# UKU208_main.net
KiCad netlist of a schematic drawn in Altium Designer
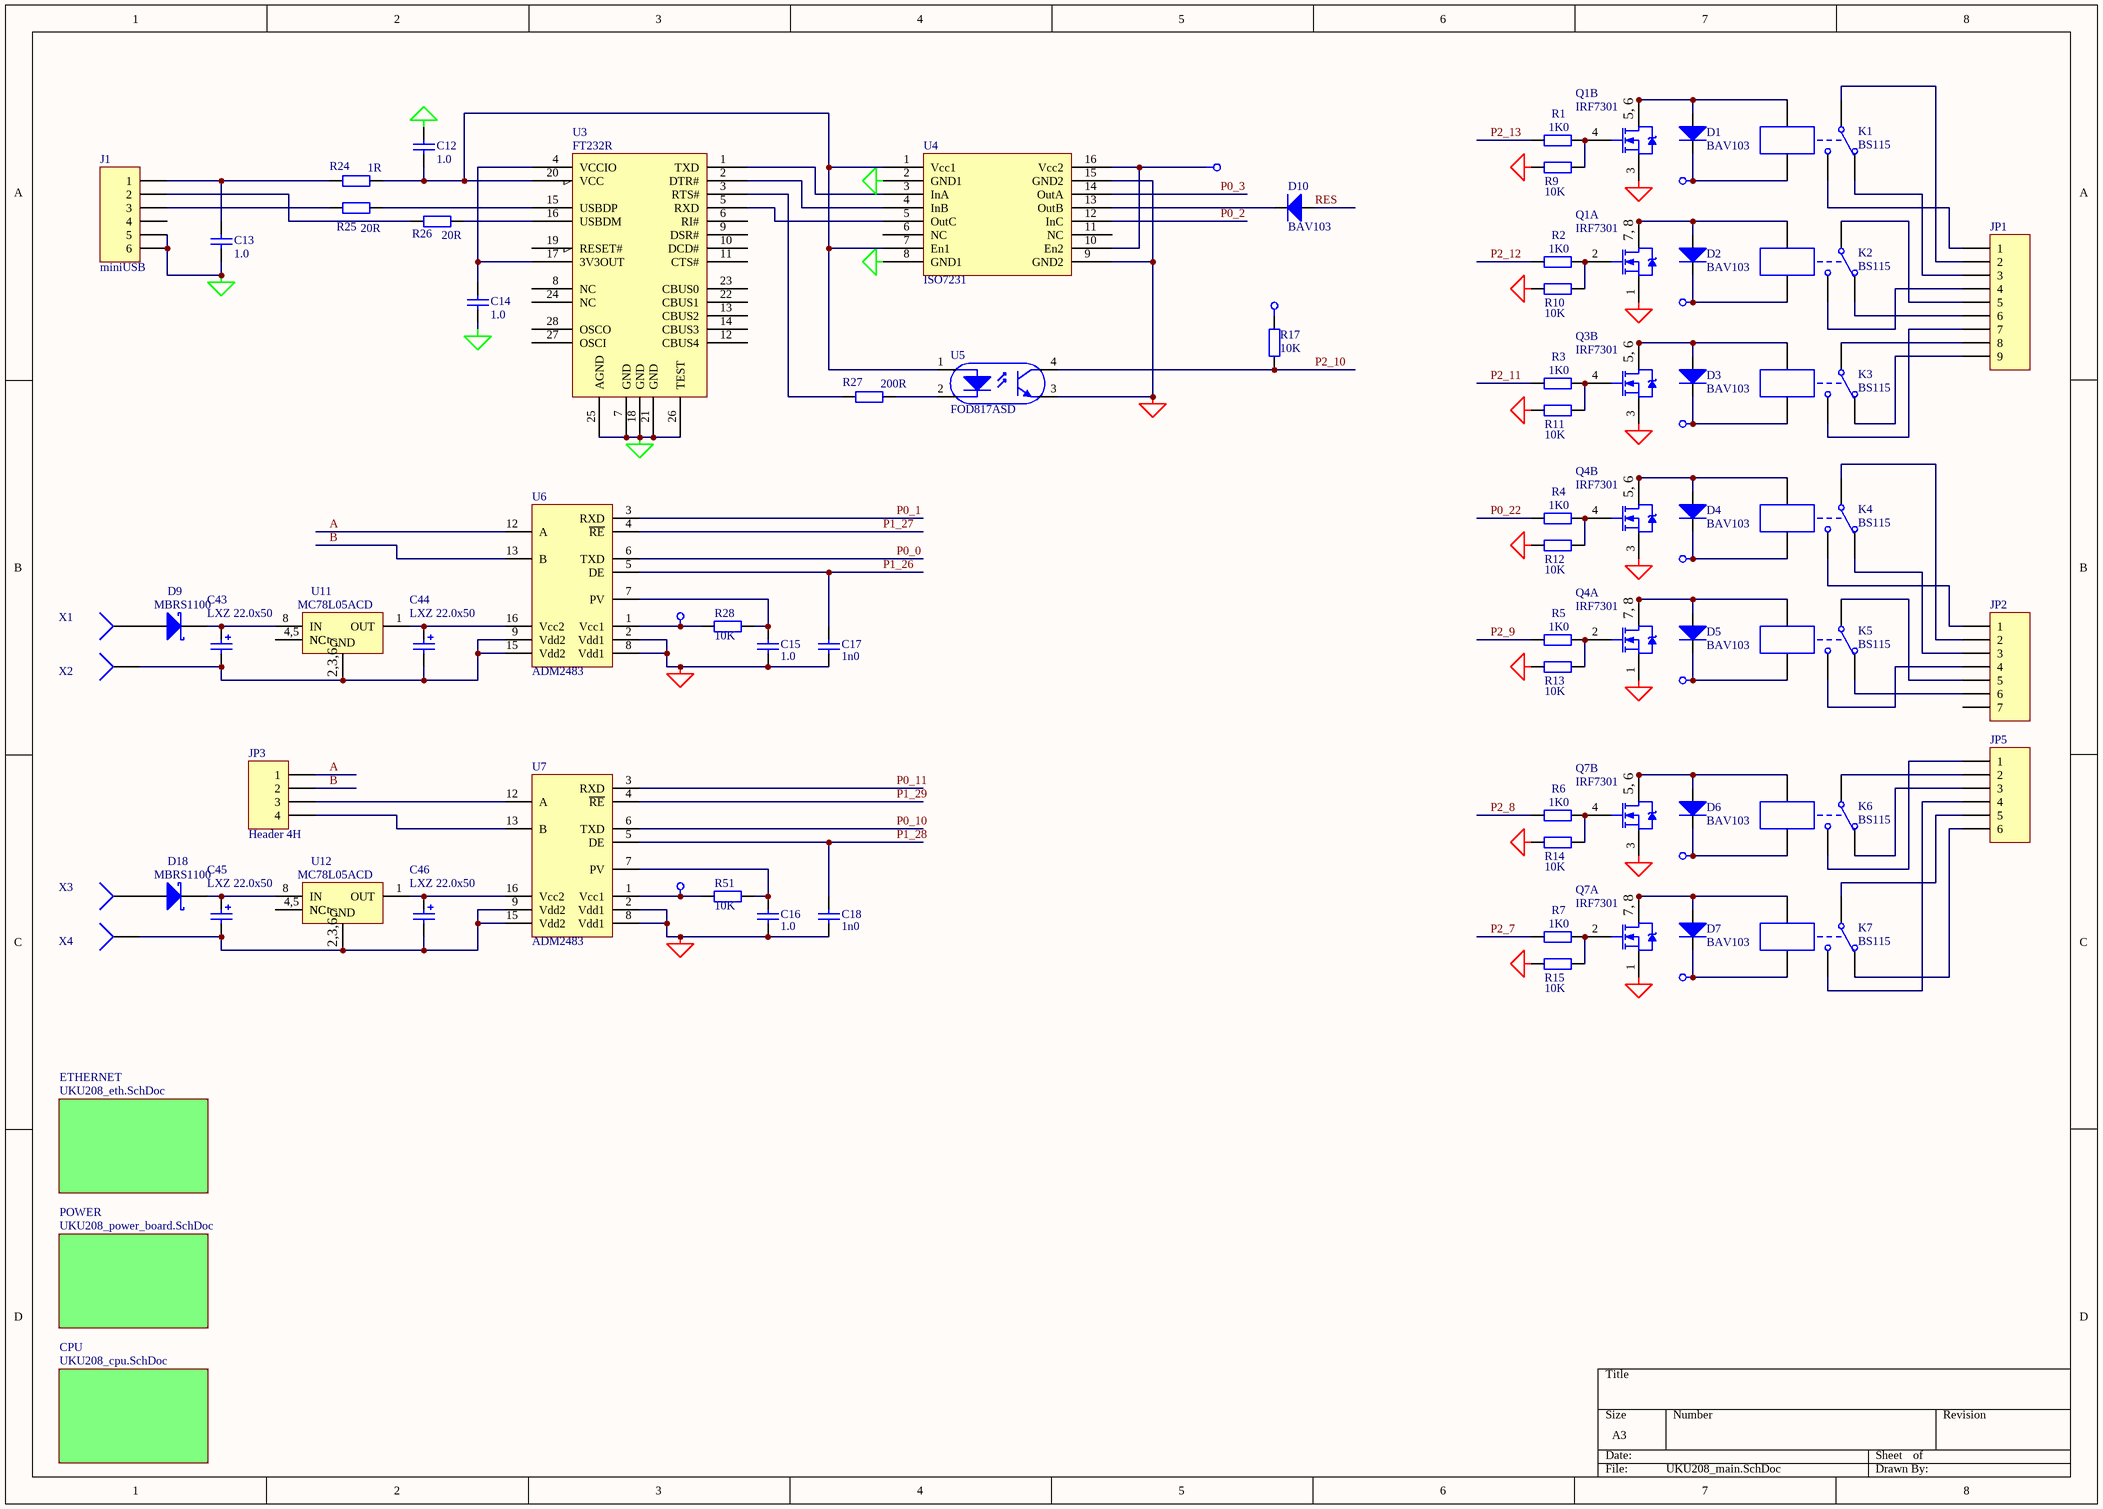
[diagram p0: UKU208_main.SchDoc]

(export (version "E")
  (design (tool "Eeschema 10.0.6"))
  (components
    (comp (ref "C12")
      (value "1.0")
      (footprint "_1206")
      (description "Capacitor (Semiconductor SIM Model)")
      (fields (field (name "MANUFACTURER") "Generic Components") (field (name "PUBLISHER") "Altium Limited"))
      (libsource (lib "Miscellaneous Devices") (part "Cap Semi"))
    )
    (comp (ref "C13")
      (value "1.0")
      (footprint "_1206")
      (description "Capacitor (Semiconductor SIM Model)")
      (fields (field (name "MANUFACTURER") "Generic Components") (field (name "PUBLISHER") "Altium Limited"))
      (libsource (lib "Miscellaneous Devices") (part "Cap Semi"))
    )
    (comp (ref "C14")
      (value "1.0")
      (footprint "_1206")
      (description "Capacitor (Semiconductor SIM Model)")
      (fields (field (name "MANUFACTURER") "Generic Components") (field (name "PUBLISHER") "Altium Limited"))
      (libsource (lib "Miscellaneous Devices") (part "Cap Semi"))
    )
    (comp (ref "C15")
      (value "1.0")
      (footprint "_1206")
      (description "Capacitor (Semiconductor SIM Model)")
      (fields (field (name "MANUFACTURER") "Generic Components") (field (name "PUBLISHER") "Altium Limited"))
      (libsource (lib "Miscellaneous Devices") (part "Cap Semi"))
    )
    (comp (ref "C16")
      (value "1.0")
      (footprint "_1206")
      (description "Capacitor (Semiconductor SIM Model)")
      (fields (field (name "MANUFACTURER") "Generic Components") (field (name "PUBLISHER") "Altium Limited"))
      (libsource (lib "Miscellaneous Devices") (part "Cap Semi"))
    )
    (comp (ref "C17")
      (value "1n0")
      (footprint "_1206")
      (description "Capacitor (Semiconductor SIM Model)")
      (fields (field (name "MANUFACTURER") "Generic Components") (field (name "PUBLISHER") "Altium Limited"))
      (libsource (lib "Miscellaneous Devices") (part "Cap Semi"))
    )
    (comp (ref "C18")
      (value "1n0")
      (footprint "_1206")
      (description "Capacitor (Semiconductor SIM Model)")
      (fields (field (name "MANUFACTURER") "Generic Components") (field (name "PUBLISHER") "Altium Limited"))
      (libsource (lib "Miscellaneous Devices") (part "Cap Semi"))
    )
    (comp (ref "C43")
      (value "LXZ 22.0x50")
      (footprint "el3")
      (description "Polarized Capacitor (Radial)")
      (fields (field (name "MANUFACTURER") "Generic Components") (field (name "PUBLISHER") "Altium Limited"))
      (libsource (lib "PAL") (part "Cap Pol1"))
    )
    (comp (ref "C44")
      (value "LXZ 22.0x50")
      (footprint "el3")
      (description "Polarized Capacitor (Radial)")
      (fields (field (name "MANUFACTURER") "Generic Components") (field (name "PUBLISHER") "Altium Limited"))
      (libsource (lib "PAL") (part "Cap Pol1"))
    )
    (comp (ref "C45")
      (value "LXZ 22.0x50")
      (footprint "el3")
      (description "Polarized Capacitor (Radial)")
      (fields (field (name "MANUFACTURER") "Generic Components") (field (name "PUBLISHER") "Altium Limited"))
      (libsource (lib "PAL") (part "Cap Pol1"))
    )
    (comp (ref "C46")
      (value "LXZ 22.0x50")
      (footprint "el3")
      (description "Polarized Capacitor (Radial)")
      (fields (field (name "MANUFACTURER") "Generic Components") (field (name "PUBLISHER") "Altium Limited"))
      (libsource (lib "PAL") (part "Cap Pol1"))
    )
    (comp (ref "D1")
      (value "BAV103")
      (footprint "_1206d")
      (description "Diode")
      (fields (field (name "MANUFACTURER") "Generic Components") (field (name "PUBLISHER") "Altium Limited"))
      (libsource (lib "PAL") (part "Diode"))
    )
    (comp (ref "D2")
      (value "BAV103")
      (footprint "_1206d")
      (description "Diode")
      (fields (field (name "MANUFACTURER") "Generic Components") (field (name "PUBLISHER") "Altium Limited"))
      (libsource (lib "PAL") (part "Diode"))
    )
    (comp (ref "D3")
      (value "BAV103")
      (footprint "_1206d")
      (description "Diode")
      (fields (field (name "MANUFACTURER") "Generic Components") (field (name "PUBLISHER") "Altium Limited"))
      (libsource (lib "PAL") (part "Diode"))
    )
    (comp (ref "D4")
      (value "BAV103")
      (footprint "_1206d")
      (description "Diode")
      (fields (field (name "MANUFACTURER") "Generic Components") (field (name "PUBLISHER") "Altium Limited"))
      (libsource (lib "PAL") (part "Diode"))
    )
    (comp (ref "D5")
      (value "BAV103")
      (footprint "_1206d")
      (description "Diode")
      (fields (field (name "MANUFACTURER") "Generic Components") (field (name "PUBLISHER") "Altium Limited"))
      (libsource (lib "PAL") (part "Diode"))
    )
    (comp (ref "D6")
      (value "BAV103")
      (footprint "_1206d")
      (description "Diode")
      (fields (field (name "MANUFACTURER") "Generic Components") (field (name "PUBLISHER") "Altium Limited"))
      (libsource (lib "PAL") (part "Diode"))
    )
    (comp (ref "D7")
      (value "BAV103")
      (footprint "_1206d")
      (description "Diode")
      (fields (field (name "MANUFACTURER") "Generic Components") (field (name "PUBLISHER") "Altium Limited"))
      (libsource (lib "PAL") (part "Diode"))
    )
    (comp (ref "D9")
      (value "MBRS1100")
      (footprint "D_6_3")
      (description "Schottky Rectifier")
      (fields
        (field (name "MANUFACTURER") "International Rectifier")
        (field (name "PUBLISHER") "Altium Limited")
      )
      (libsource (lib "IR Discrete Diode") (part "10BQ015"))
    )
    (comp (ref "D10")
      (value "BAV103")
      (footprint "_1206d")
      (description "Diode")
      (fields (field (name "MANUFACTURER") "Generic Components") (field (name "PUBLISHER") "Altium Limited"))
      (libsource (lib "PAL") (part "Diode"))
    )
    (comp (ref "D18")
      (value "MBRS1100")
      (footprint "D_6_3")
      (description "Schottky Rectifier")
      (fields
        (field (name "MANUFACTURER") "International Rectifier")
        (field (name "PUBLISHER") "Altium Limited")
      )
      (libsource (lib "IR Discrete Diode") (part "10BQ015"))
    )
    (comp (ref "J1")
      (value "miniUSB")
      (footprint "USBmini")
      (description "Header, 6-Pin")
      (fields (field (name "PUBLISHER") "Altium Limited"))
      (libsource (lib "Miscellaneous Connectors") (part "Header 6"))
    )
    (comp (ref "JP1")
      (value "MHDR1X9")
      (footprint "2EDGR-5.08-9P")
      (description "Header, 9-Pin")
      (fields (field (name "MANUFACTURER") "Generic Components") (field (name "PUBLISHER") "Altium Limited"))
      (libsource (lib "Miscellaneous Connectors") (part "MHDR1X9"))
    )
    (comp (ref "JP2")
      (value "MHDR1X7")
      (footprint "2EDGR-5.08-7P")
      (description "Header, 7-Pin")
      (fields (field (name "MANUFACTURER") "Generic Components") (field (name "PUBLISHER") "Altium Limited"))
      (libsource (lib "Miscellaneous Connectors") (part "MHDR1X7"))
    )
    (comp (ref "JP3")
      (value "Header 4H")
      (footprint "2EDGR-5.08-4P")
      (description "Header, 4-Pin,  Right Angle")
      (fields (field (name "MANUFACTURER") "Generic Components") (field (name "PUBLISHER") "Altium Limited"))
      (libsource (lib "Miscellaneous Connectors") (part "Header 4H"))
    )
    (comp (ref "JP5")
      (value "MHDR1X6")
      (footprint "2EDGR-5.08-6P")
      (description "Header, 6-Pin")
      (fields (field (name "MANUFACTURER") "Generic Components") (field (name "PUBLISHER") "Altium Limited"))
      (libsource (lib "Miscellaneous Connectors") (part "MHDR1X6"))
    )
    (comp (ref "K1")
      (value "BS115")
      (footprint "bs115")
      (description "Single-Pole Dual-Throw Relay")
      (fields (field (name "MANUFACTURER") "Generic Components") (field (name "PUBLISHER") "Altium Limited"))
      (libsource (lib "PAL") (part "BS115"))
    )
    (comp (ref "K2")
      (value "BS115")
      (footprint "bs115")
      (description "Single-Pole Dual-Throw Relay")
      (fields (field (name "MANUFACTURER") "Generic Components") (field (name "PUBLISHER") "Altium Limited"))
      (libsource (lib "PAL") (part "BS115"))
    )
    (comp (ref "K3")
      (value "BS115")
      (footprint "bs115")
      (description "Single-Pole Dual-Throw Relay")
      (fields (field (name "MANUFACTURER") "Generic Components") (field (name "PUBLISHER") "Altium Limited"))
      (libsource (lib "PAL") (part "BS115"))
    )
    (comp (ref "K4")
      (value "BS115")
      (footprint "bs115")
      (description "Single-Pole Dual-Throw Relay")
      (fields (field (name "MANUFACTURER") "Generic Components") (field (name "PUBLISHER") "Altium Limited"))
      (libsource (lib "PAL") (part "BS115"))
    )
    (comp (ref "K5")
      (value "BS115")
      (footprint "bs115")
      (description "Single-Pole Dual-Throw Relay")
      (fields (field (name "MANUFACTURER") "Generic Components") (field (name "PUBLISHER") "Altium Limited"))
      (libsource (lib "PAL") (part "BS115"))
    )
    (comp (ref "K6")
      (value "BS115")
      (footprint "bs115")
      (description "Single-Pole Dual-Throw Relay")
      (fields (field (name "MANUFACTURER") "Generic Components") (field (name "PUBLISHER") "Altium Limited"))
      (libsource (lib "PAL") (part "BS115"))
    )
    (comp (ref "K7")
      (value "BS115")
      (footprint "bs115")
      (description "Single-Pole Dual-Throw Relay")
      (fields (field (name "MANUFACTURER") "Generic Components") (field (name "PUBLISHER") "Altium Limited"))
      (libsource (lib "PAL") (part "BS115"))
    )
    (comp (ref "Q1")
      (value "IRF7301")
      (footprint "SO-G8/Y2.2")
      (description "FET")
      (fields
        (field (name "MANUFACTURER") "International Rectifier")
        (field (name "PUBLISHER") "Altium Limited")
      )
      (libsource (lib "IR Discrete MOSFET") (part "IRF7301"))
    )
    (comp (ref "Q3")
      (value "IRF7301")
      (footprint "SO-G8/Y2.2")
      (description "FET")
      (fields
        (field (name "MANUFACTURER") "International Rectifier")
        (field (name "PUBLISHER") "Altium Limited")
      )
      (libsource (lib "IR Discrete MOSFET") (part "IRF7301"))
    )
    (comp (ref "Q4")
      (value "IRF7301")
      (footprint "SO-G8/Y2.2")
      (description "FET")
      (fields
        (field (name "MANUFACTURER") "International Rectifier")
        (field (name "PUBLISHER") "Altium Limited")
      )
      (libsource (lib "IR Discrete MOSFET") (part "IRF7301"))
    )
    (comp (ref "Q7")
      (value "IRF7301")
      (footprint "SO-G8/Y2.2")
      (description "FET")
      (fields
        (field (name "MANUFACTURER") "International Rectifier")
        (field (name "PUBLISHER") "Altium Limited")
      )
      (libsource (lib "IR Discrete MOSFET") (part "IRF7301"))
    )
    (comp (ref "R1")
      (value "1K0")
      (footprint "_1206")
      (description "Resistor")
      (fields (field (name "MANUFACTURER") "Generic Components") (field (name "PUBLISHER") "Altium Limited"))
      (libsource (lib "Miscellaneous Devices") (part "Res2"))
    )
    (comp (ref "R2")
      (value "1K0")
      (footprint "_1206")
      (description "Resistor")
      (fields (field (name "MANUFACTURER") "Generic Components") (field (name "PUBLISHER") "Altium Limited"))
      (libsource (lib "Miscellaneous Devices") (part "Res2"))
    )
    (comp (ref "R3")
      (value "1K0")
      (footprint "_1206")
      (description "Resistor")
      (fields (field (name "MANUFACTURER") "Generic Components") (field (name "PUBLISHER") "Altium Limited"))
      (libsource (lib "Miscellaneous Devices") (part "Res2"))
    )
    (comp (ref "R4")
      (value "1K0")
      (footprint "_1206")
      (description "Resistor")
      (fields (field (name "MANUFACTURER") "Generic Components") (field (name "PUBLISHER") "Altium Limited"))
      (libsource (lib "Miscellaneous Devices") (part "Res2"))
    )
    (comp (ref "R5")
      (value "1K0")
      (footprint "_1206")
      (description "Resistor")
      (fields (field (name "MANUFACTURER") "Generic Components") (field (name "PUBLISHER") "Altium Limited"))
      (libsource (lib "Miscellaneous Devices") (part "Res2"))
    )
    (comp (ref "R6")
      (value "1K0")
      (footprint "_1206")
      (description "Resistor")
      (fields (field (name "MANUFACTURER") "Generic Components") (field (name "PUBLISHER") "Altium Limited"))
      (libsource (lib "Miscellaneous Devices") (part "Res2"))
    )
    (comp (ref "R7")
      (value "1K0")
      (footprint "_1206")
      (description "Resistor")
      (fields (field (name "MANUFACTURER") "Generic Components") (field (name "PUBLISHER") "Altium Limited"))
      (libsource (lib "Miscellaneous Devices") (part "Res2"))
    )
    (comp (ref "R9")
      (value "10K")
      (footprint "_1206")
      (description "Resistor")
      (fields (field (name "MANUFACTURER") "Generic Components") (field (name "PUBLISHER") "Altium Limited"))
      (libsource (lib "Miscellaneous Devices") (part "Res2"))
    )
    (comp (ref "R10")
      (value "10K")
      (footprint "_1206")
      (description "Resistor")
      (fields (field (name "MANUFACTURER") "Generic Components") (field (name "PUBLISHER") "Altium Limited"))
      (libsource (lib "Miscellaneous Devices") (part "Res2"))
    )
    (comp (ref "R11")
      (value "10K")
      (footprint "_1206")
      (description "Resistor")
      (fields (field (name "MANUFACTURER") "Generic Components") (field (name "PUBLISHER") "Altium Limited"))
      (libsource (lib "Miscellaneous Devices") (part "Res2"))
    )
    (comp (ref "R12")
      (value "10K")
      (footprint "_1206")
      (description "Resistor")
      (fields (field (name "MANUFACTURER") "Generic Components") (field (name "PUBLISHER") "Altium Limited"))
      (libsource (lib "Miscellaneous Devices") (part "Res2"))
    )
    (comp (ref "R13")
      (value "10K")
      (footprint "_1206")
      (description "Resistor")
      (fields (field (name "MANUFACTURER") "Generic Components") (field (name "PUBLISHER") "Altium Limited"))
      (libsource (lib "Miscellaneous Devices") (part "Res2"))
    )
    (comp (ref "R14")
      (value "10K")
      (footprint "_1206")
      (description "Resistor")
      (fields (field (name "MANUFACTURER") "Generic Components") (field (name "PUBLISHER") "Altium Limited"))
      (libsource (lib "Miscellaneous Devices") (part "Res2"))
    )
    (comp (ref "R15")
      (value "10K")
      (footprint "_1206")
      (description "Resistor")
      (fields (field (name "MANUFACTURER") "Generic Components") (field (name "PUBLISHER") "Altium Limited"))
      (libsource (lib "Miscellaneous Devices") (part "Res2"))
    )
    (comp (ref "R17")
      (value "10K")
      (footprint "_1206")
      (description "Resistor")
      (fields (field (name "MANUFACTURER") "Generic Components") (field (name "PUBLISHER") "Altium Limited"))
      (libsource (lib "") (part "Res2_1"))
    )
    (comp (ref "R24") (value "1R") (footprint "_1206") (libsource (lib "igorenja") (part "RES")))
    (comp (ref "R25") (value "20R") (footprint "_1206") (libsource (lib "igorenja") (part "RES")))
    (comp (ref "R26") (value "20R") (footprint "_1206") (libsource (lib "igorenja") (part "RES")))
    (comp (ref "R27") (value "200R") (footprint "_1206") (libsource (lib "igorenja") (part "RES")))
    (comp (ref "R28")
      (value "10K")
      (footprint "_1206")
      (description "Resistor")
      (fields (field (name "MANUFACTURER") "Generic Components") (field (name "PUBLISHER") "Altium Limited"))
      (libsource (lib "") (part "Res2_2"))
    )
    (comp (ref "R51")
      (value "10K")
      (footprint "_1206")
      (description "Resistor")
      (fields (field (name "MANUFACTURER") "Generic Components") (field (name "PUBLISHER") "Altium Limited"))
      (libsource (lib "") (part "Res2_2"))
    )
    (comp (ref "U3")
      (value "FT232R")
      (footprint "SOP65P780-28L")
      (libsource (lib "igorenja") (part "FT232R"))
    )
    (comp (ref "U4") (value "ISO7231") (footprint "SO-G16/D10.4") (libsource (lib "PAL") (part "ISO7231")))
    (comp (ref "U5") (value "FOD817ASD") (footprint "FOD817ASD") (libsource (lib "PAL") (part "F00817ASD")))
    (comp (ref "U6") (value "ADM2483") (footprint "SO-G16/D10.4") (libsource (lib "PAL") (part "ADM2483")))
    (comp (ref "U7") (value "ADM2483") (footprint "SO-G16/D10.4") (libsource (lib "PAL") (part "ADM2483")))
    (comp (ref "U11")
      (value "MC78L05ACD")
      (footprint "SO-G8")
      (description "3-Terminal Low-Current Positive Fixed Voltage Regulator")
      (fields (field (name "MANUFACTURER") "Motorola") (field (name "PUBLISHER") "Altium Limited"))
      (libsource (lib "Motorola Power Management Voltage Regulator") (part "MC78L05ACD"))
    )
    (comp (ref "U12")
      (value "MC78L05ACD")
      (footprint "SO-G8")
      (description "3-Terminal Low-Current Positive Fixed Voltage Regulator")
      (fields (field (name "MANUFACTURER") "Motorola") (field (name "PUBLISHER") "Altium Limited"))
      (libsource (lib "Motorola Power Management Voltage Regulator") (part "MC78L05ACD"))
    )
    (comp (ref "X1")
      (value "~")
      (footprint "PIN1")
      (description "Socket")
      (fields (field (name "MANUFACTURER") "Generic Components") (field (name "PUBLISHER") "Altium Limited"))
      (libsource (lib "Miscellaneous Connectors") (part "Socket"))
    )
    (comp (ref "X2")
      (value "~")
      (footprint "PIN1")
      (description "Socket")
      (fields (field (name "MANUFACTURER") "Generic Components") (field (name "PUBLISHER") "Altium Limited"))
      (libsource (lib "Miscellaneous Connectors") (part "Socket"))
    )
    (comp (ref "X3")
      (value "~")
      (footprint "PIN1")
      (description "Socket")
      (fields (field (name "MANUFACTURER") "Generic Components") (field (name "PUBLISHER") "Altium Limited"))
      (libsource (lib "Miscellaneous Connectors") (part "Socket"))
    )
    (comp (ref "X4")
      (value "~")
      (footprint "PIN1")
      (description "Socket")
      (fields (field (name "MANUFACTURER") "Generic Components") (field (name "PUBLISHER") "Altium Limited"))
      (libsource (lib "Miscellaneous Connectors") (part "Socket"))
    )
  )
  (nets
    (net (code "1") (name "+3v3") (class "Default")
      (node (ref "R17") (pin "2") (pinfunction "2_2") (pintype "passive"))
    )
    (net (code "2") (name "+5v") (class "Default")
      (node (ref "D1") (pin "2") (pinfunction "K_2") (pintype "passive"))
      (node (ref "D2") (pin "2") (pinfunction "K_2") (pintype "passive"))
      (node (ref "D3") (pin "2") (pinfunction "K_2") (pintype "passive"))
      (node (ref "D4") (pin "2") (pinfunction "K_2") (pintype "passive"))
      (node (ref "D5") (pin "2") (pinfunction "K_2") (pintype "passive"))
      (node (ref "D6") (pin "2") (pinfunction "K_2") (pintype "passive"))
      (node (ref "D7") (pin "2") (pinfunction "K_2") (pintype "passive"))
      (node (ref "K1") (pin "5") (pinfunction "5_5") (pintype "passive"))
      (node (ref "K2") (pin "5") (pinfunction "5_5") (pintype "passive"))
      (node (ref "K3") (pin "5") (pinfunction "5_5") (pintype "passive"))
      (node (ref "K4") (pin "5") (pinfunction "5_5") (pintype "passive"))
      (node (ref "K5") (pin "5") (pinfunction "5_5") (pintype "passive"))
      (node (ref "K6") (pin "5") (pinfunction "5_5") (pintype "passive"))
      (node (ref "K7") (pin "5") (pinfunction "5_5") (pintype "passive"))
      (node (ref "R28") (pin "1") (pinfunction "1_1") (pintype "passive"))
      (node (ref "R51") (pin "1") (pinfunction "1_1") (pintype "passive"))
      (node (ref "U4") (pin "10") (pinfunction "En2_10") (pintype "passive"))
      (node (ref "U4") (pin "16") (pinfunction "Vcc2_16") (pintype "passive"))
      (node (ref "U6") (pin "1") (pinfunction "Vcc1_1") (pintype "passive"))
      (node (ref "U7") (pin "1") (pinfunction "Vcc1_1") (pintype "passive"))
    )
    (net (code "3") (name "/A") (class "Default")
      (node (ref "JP3") (pin "1") (pinfunction "1_1") (pintype "passive"))
      (node (ref "U6") (pin "12") (pinfunction "A_12") (pintype "passive"))
    )
    (net (code "4") (name "/B") (class "Default")
      (node (ref "JP3") (pin "2") (pinfunction "2_2") (pintype "passive"))
      (node (ref "U6") (pin "13") (pinfunction "B_13") (pintype "passive"))
    )
    (net (code "5") (name "/P0_0") (class "Default")
      (node (ref "U6") (pin "6") (pinfunction "TXD_6") (pintype "passive"))
    )
    (net (code "6") (name "/P0_1") (class "Default")
      (node (ref "U6") (pin "3") (pinfunction "RXD_3") (pintype "passive"))
    )
    (net (code "7") (name "/P0_2") (class "Default")
      (node (ref "U4") (pin "12") (pinfunction "InC_12") (pintype "passive"))
    )
    (net (code "8") (name "/P0_3") (class "Default")
      (node (ref "U4") (pin "14") (pinfunction "OutA_14") (pintype "passive"))
    )
    (net (code "9") (name "/P0_10") (class "Default")
      (node (ref "U7") (pin "6") (pinfunction "TXD_6") (pintype "passive"))
    )
    (net (code "10") (name "/P0_11") (class "Default")
      (node (ref "U7") (pin "3") (pinfunction "RXD_3") (pintype "passive"))
    )
    (net (code "11") (name "/P0_22") (class "Default")
      (node (ref "R4") (pin "1") (pinfunction "1_1") (pintype "passive"))
    )
    (net (code "12") (name "/P1_26") (class "Default")
      (node (ref "C17") (pin "2") (pinfunction "2_2") (pintype "passive"))
      (node (ref "U6") (pin "5") (pinfunction "DE_5") (pintype "passive"))
    )
    (net (code "13") (name "/P1_27") (class "Default")
      (node (ref "U6") (pin "4") (pinfunction "~{RE}_4") (pintype "passive"))
    )
    (net (code "14") (name "/P1_28") (class "Default")
      (node (ref "C18") (pin "2") (pinfunction "2_2") (pintype "passive"))
      (node (ref "U7") (pin "5") (pinfunction "DE_5") (pintype "passive"))
    )
    (net (code "15") (name "/P1_29") (class "Default")
      (node (ref "U7") (pin "4") (pinfunction "~{RE}_4") (pintype "passive"))
    )
    (net (code "16") (name "/P2_7") (class "Default")
      (node (ref "R7") (pin "1") (pinfunction "1_1") (pintype "passive"))
    )
    (net (code "17") (name "/P2_8") (class "Default")
      (node (ref "R6") (pin "1") (pinfunction "1_1") (pintype "passive"))
    )
    (net (code "18") (name "/P2_9") (class "Default")
      (node (ref "R5") (pin "1") (pinfunction "1_1") (pintype "passive"))
    )
    (net (code "19") (name "/P2_10") (class "Default")
      (node (ref "R17") (pin "1") (pinfunction "1_1") (pintype "passive"))
      (node (ref "U5") (pin "4") (pinfunction "2_4") (pintype "passive"))
    )
    (net (code "20") (name "/P2_11") (class "Default")
      (node (ref "R3") (pin "1") (pinfunction "1_1") (pintype "passive"))
    )
    (net (code "21") (name "/P2_12") (class "Default")
      (node (ref "R2") (pin "1") (pinfunction "1_1") (pintype "passive"))
    )
    (net (code "22") (name "/P2_13") (class "Default")
      (node (ref "R1") (pin "1") (pinfunction "1_1") (pintype "passive"))
    )
    (net (code "23") (name "/RES") (class "Default")
      (node (ref "D10") (pin "1") (pinfunction "A_1") (pintype "passive"))
    )
    (net (code "24") (name "GND") (class "Default")
      (node (ref "C15") (pin "1") (pinfunction "1_1") (pintype "passive"))
      (node (ref "C16") (pin "1") (pinfunction "1_1") (pintype "passive"))
      (node (ref "C17") (pin "1") (pinfunction "1_1") (pintype "passive"))
      (node (ref "C18") (pin "1") (pinfunction "1_1") (pintype "passive"))
      (node (ref "Q1") (pin "1") (pinfunction "S_1") (pintype "passive"))
      (node (ref "Q1") (pin "3") (pinfunction "S_3") (pintype "passive"))
      (node (ref "Q3") (pin "3") (pinfunction "S_3") (pintype "passive"))
      (node (ref "Q4") (pin "1") (pinfunction "S_1") (pintype "passive"))
      (node (ref "Q4") (pin "3") (pinfunction "S_3") (pintype "passive"))
      (node (ref "Q7") (pin "1") (pinfunction "S_1") (pintype "passive"))
      (node (ref "Q7") (pin "3") (pinfunction "S_3") (pintype "passive"))
      (node (ref "R10") (pin "1") (pinfunction "1_1") (pintype "passive"))
      (node (ref "R11") (pin "1") (pinfunction "1_1") (pintype "passive"))
      (node (ref "R12") (pin "1") (pinfunction "1_1") (pintype "passive"))
      (node (ref "R13") (pin "1") (pinfunction "1_1") (pintype "passive"))
      (node (ref "R14") (pin "1") (pinfunction "1_1") (pintype "passive"))
      (node (ref "R15") (pin "1") (pinfunction "1_1") (pintype "passive"))
      (node (ref "R9") (pin "1") (pinfunction "1_1") (pintype "passive"))
      (node (ref "U4") (pin "15") (pinfunction "GND2_15") (pintype "passive"))
      (node (ref "U4") (pin "9") (pinfunction "GND2_9") (pintype "passive"))
      (node (ref "U5") (pin "3") (pinfunction "4_3") (pintype "passive"))
      (node (ref "U6") (pin "2") (pinfunction "Vdd1_2") (pintype "passive"))
      (node (ref "U6") (pin "8") (pinfunction "Vdd1_8") (pintype "passive"))
      (node (ref "U7") (pin "2") (pinfunction "Vdd1_2") (pintype "passive"))
      (node (ref "U7") (pin "8") (pinfunction "Vdd1_8") (pintype "passive"))
    )
    (net (code "25") (name "GND_USB") (class "Default")
      (node (ref "C12") (pin "1") (pinfunction "1_1") (pintype "passive"))
      (node (ref "C13") (pin "1") (pinfunction "1_1") (pintype "passive"))
      (node (ref "C14") (pin "1") (pinfunction "1_1") (pintype "passive"))
      (node (ref "J1") (pin "5") (pinfunction "5_5") (pintype "passive"))
      (node (ref "J1") (pin "6") (pinfunction "6_6") (pintype "passive"))
      (node (ref "U3") (pin "18") (pinfunction "GND_18") (pintype "passive"))
      (node (ref "U3") (pin "21") (pinfunction "GND_21") (pintype "passive"))
      (node (ref "U3") (pin "25") (pinfunction "AGND_25") (pintype "passive"))
      (node (ref "U3") (pin "26") (pinfunction "TEST_26") (pintype "passive"))
      (node (ref "U3") (pin "7") (pinfunction "GND_7") (pintype "passive"))
      (node (ref "U4") (pin "2") (pinfunction "GND1_2") (pintype "passive"))
      (node (ref "U4") (pin "8") (pinfunction "GND1_8") (pintype "passive"))
    )
    (net (code "26") (name "Net-(C13-Pad2)") (class "Default")
      (node (ref "C13") (pin "2") (pinfunction "2_2") (pintype "passive"))
      (node (ref "J1") (pin "1") (pinfunction "1_1") (pintype "passive"))
      (node (ref "R24") (pin "1") (pinfunction "1_1") (pintype "passive"))
    )
    (net (code "27") (name "Net-(C43-Pad2)") (class "Default")
      (node (ref "C43") (pin "2") (pinfunction "2_2") (pintype "passive"))
      (node (ref "C44") (pin "2") (pinfunction "2_2") (pintype "passive"))
      (node (ref "U11") (pin "2") (pinfunction "GND_2") (pintype "power_in"))
      (node (ref "U11") (pin "3") (pinfunction "GND_3") (pintype "power_in"))
      (node (ref "U11") (pin "6") (pinfunction "GND_6") (pintype "power_in"))
      (node (ref "U11") (pin "7") (pinfunction "GND_7") (pintype "power_in"))
      (node (ref "U6") (pin "15") (pinfunction "Vdd2_15") (pintype "passive"))
      (node (ref "U6") (pin "9") (pinfunction "Vdd2_9") (pintype "passive"))
      (node (ref "X2") (pin "1") (pinfunction "1_1") (pintype "passive"))
    )
    (net (code "28") (name "Net-(C45-Pad2)") (class "Default")
      (node (ref "C45") (pin "2") (pinfunction "2_2") (pintype "passive"))
      (node (ref "C46") (pin "2") (pinfunction "2_2") (pintype "passive"))
      (node (ref "U12") (pin "2") (pinfunction "GND_2") (pintype "power_in"))
      (node (ref "U12") (pin "3") (pinfunction "GND_3") (pintype "power_in"))
      (node (ref "U12") (pin "6") (pinfunction "GND_6") (pintype "power_in"))
      (node (ref "U12") (pin "7") (pinfunction "GND_7") (pintype "power_in"))
      (node (ref "U7") (pin "15") (pinfunction "Vdd2_15") (pintype "passive"))
      (node (ref "U7") (pin "9") (pinfunction "Vdd2_9") (pintype "passive"))
      (node (ref "X4") (pin "1") (pinfunction "1_1") (pintype "passive"))
    )
    (net (code "29") (name "Net-(D1-A)") (class "Default")
      (node (ref "D1") (pin "1") (pinfunction "A_1") (pintype "passive"))
      (node (ref "K1") (pin "4") (pinfunction "4_4") (pintype "passive"))
      (node (ref "Q1") (pin "5") (pinfunction "D_5") (pintype "passive"))
      (node (ref "Q1") (pin "6") (pinfunction "D_6") (pintype "passive"))
    )
    (net (code "30") (name "Net-(D2-A)") (class "Default")
      (node (ref "D2") (pin "1") (pinfunction "A_1") (pintype "passive"))
      (node (ref "K2") (pin "4") (pinfunction "4_4") (pintype "passive"))
      (node (ref "Q1") (pin "7") (pinfunction "D_7") (pintype "passive"))
      (node (ref "Q1") (pin "8") (pinfunction "D_8") (pintype "passive"))
    )
    (net (code "31") (name "Net-(D3-A)") (class "Default")
      (node (ref "D3") (pin "1") (pinfunction "A_1") (pintype "passive"))
      (node (ref "K3") (pin "4") (pinfunction "4_4") (pintype "passive"))
      (node (ref "Q3") (pin "5") (pinfunction "D_5") (pintype "passive"))
      (node (ref "Q3") (pin "6") (pinfunction "D_6") (pintype "passive"))
    )
    (net (code "32") (name "Net-(D4-A)") (class "Default")
      (node (ref "D4") (pin "1") (pinfunction "A_1") (pintype "passive"))
      (node (ref "K4") (pin "4") (pinfunction "4_4") (pintype "passive"))
      (node (ref "Q4") (pin "5") (pinfunction "D_5") (pintype "passive"))
      (node (ref "Q4") (pin "6") (pinfunction "D_6") (pintype "passive"))
    )
    (net (code "33") (name "Net-(D5-A)") (class "Default")
      (node (ref "D5") (pin "1") (pinfunction "A_1") (pintype "passive"))
      (node (ref "K5") (pin "4") (pinfunction "4_4") (pintype "passive"))
      (node (ref "Q4") (pin "7") (pinfunction "D_7") (pintype "passive"))
      (node (ref "Q4") (pin "8") (pinfunction "D_8") (pintype "passive"))
    )
    (net (code "34") (name "Net-(D6-A)") (class "Default")
      (node (ref "D6") (pin "1") (pinfunction "A_1") (pintype "passive"))
      (node (ref "K6") (pin "4") (pinfunction "4_4") (pintype "passive"))
      (node (ref "Q7") (pin "5") (pinfunction "D_5") (pintype "passive"))
      (node (ref "Q7") (pin "6") (pinfunction "D_6") (pintype "passive"))
    )
    (net (code "35") (name "Net-(D7-A)") (class "Default")
      (node (ref "D7") (pin "1") (pinfunction "A_1") (pintype "passive"))
      (node (ref "K7") (pin "4") (pinfunction "4_4") (pintype "passive"))
      (node (ref "Q7") (pin "7") (pinfunction "D_7") (pintype "passive"))
      (node (ref "Q7") (pin "8") (pinfunction "D_8") (pintype "passive"))
    )
    (net (code "36") (name "Net-(D9-A)") (class "Default")
      (node (ref "D9") (pin "1") (pinfunction "A_1") (pintype "passive"))
      (node (ref "X1") (pin "1") (pinfunction "1_1") (pintype "passive"))
    )
    (net (code "37") (name "Net-(D9-K)") (class "Default")
      (node (ref "C43") (pin "1") (pinfunction "1_1") (pintype "passive"))
      (node (ref "D9") (pin "2") (pinfunction "K_2") (pintype "passive"))
      (node (ref "U11") (pin "8") (pinfunction "IN_8") (pintype "power_in"))
    )
    (net (code "38") (name "Net-(D10-K)") (class "Default")
      (node (ref "D10") (pin "2") (pinfunction "K_2") (pintype "passive"))
      (node (ref "U4") (pin "13") (pinfunction "OutB_13") (pintype "passive"))
    )
    (net (code "39") (name "Net-(D18-A)") (class "Default")
      (node (ref "D18") (pin "1") (pinfunction "A_1") (pintype "passive"))
      (node (ref "X3") (pin "1") (pinfunction "1_1") (pintype "passive"))
    )
    (net (code "40") (name "Net-(D18-K)") (class "Default")
      (node (ref "C45") (pin "1") (pinfunction "1_1") (pintype "passive"))
      (node (ref "D18") (pin "2") (pinfunction "K_2") (pintype "passive"))
      (node (ref "U12") (pin "8") (pinfunction "IN_8") (pintype "power_in"))
    )
    (net (code "41") (name "Net-(J1-Pad2)") (class "Default")
      (node (ref "J1") (pin "2") (pinfunction "2_2") (pintype "passive"))
      (node (ref "R26") (pin "1") (pinfunction "1_1") (pintype "passive"))
    )
    (net (code "42") (name "Net-(J1-Pad3)") (class "Default")
      (node (ref "J1") (pin "3") (pinfunction "3_3") (pintype "passive"))
      (node (ref "R25") (pin "1") (pinfunction "1_1") (pintype "passive"))
    )
    (net (code "43") (name "Net-(JP1-Pad1)") (class "Default")
      (node (ref "JP1") (pin "1") (pinfunction "1_1") (pintype "passive"))
      (node (ref "K1") (pin "3") (pinfunction "3_3") (pintype "passive"))
    )
    (net (code "44") (name "Net-(JP1-Pad2)") (class "Default")
      (node (ref "JP1") (pin "2") (pinfunction "2_2") (pintype "passive"))
      (node (ref "K1") (pin "1") (pinfunction "1_1") (pintype "passive"))
    )
    (net (code "45") (name "Net-(JP1-Pad3)") (class "Default")
      (node (ref "JP1") (pin "3") (pinfunction "3_3") (pintype "passive"))
      (node (ref "K1") (pin "2") (pinfunction "2_2") (pintype "passive"))
    )
    (net (code "46") (name "Net-(JP1-Pad4)") (class "Default")
      (node (ref "JP1") (pin "4") (pinfunction "4_4") (pintype "passive"))
      (node (ref "K2") (pin "3") (pinfunction "3_3") (pintype "passive"))
    )
    (net (code "47") (name "Net-(JP1-Pad5)") (class "Default")
      (node (ref "JP1") (pin "5") (pinfunction "5_5") (pintype "passive"))
      (node (ref "K2") (pin "1") (pinfunction "1_1") (pintype "passive"))
    )
    (net (code "48") (name "Net-(JP1-Pad6)") (class "Default")
      (node (ref "JP1") (pin "6") (pinfunction "6_6") (pintype "passive"))
      (node (ref "K2") (pin "2") (pinfunction "2_2") (pintype "passive"))
    )
    (net (code "49") (name "Net-(JP1-Pad7)") (class "Default")
      (node (ref "JP1") (pin "7") (pinfunction "7_7") (pintype "passive"))
      (node (ref "K3") (pin "3") (pinfunction "3_3") (pintype "passive"))
    )
    (net (code "50") (name "Net-(JP1-Pad8)") (class "Default")
      (node (ref "JP1") (pin "8") (pinfunction "8_8") (pintype "passive"))
      (node (ref "K3") (pin "1") (pinfunction "1_1") (pintype "passive"))
    )
    (net (code "51") (name "Net-(JP1-Pad9)") (class "Default")
      (node (ref "JP1") (pin "9") (pinfunction "9_9") (pintype "passive"))
      (node (ref "K3") (pin "2") (pinfunction "2_2") (pintype "passive"))
    )
    (net (code "52") (name "Net-(JP2-Pad1)") (class "Default")
      (node (ref "JP2") (pin "1") (pinfunction "1_1") (pintype "passive"))
      (node (ref "K4") (pin "3") (pinfunction "3_3") (pintype "passive"))
    )
    (net (code "53") (name "Net-(JP2-Pad2)") (class "Default")
      (node (ref "JP2") (pin "2") (pinfunction "2_2") (pintype "passive"))
      (node (ref "K4") (pin "1") (pinfunction "1_1") (pintype "passive"))
    )
    (net (code "54") (name "Net-(JP2-Pad3)") (class "Default")
      (node (ref "JP2") (pin "3") (pinfunction "3_3") (pintype "passive"))
      (node (ref "K4") (pin "2") (pinfunction "2_2") (pintype "passive"))
    )
    (net (code "55") (name "Net-(JP2-Pad4)") (class "Default")
      (node (ref "JP2") (pin "4") (pinfunction "4_4") (pintype "passive"))
      (node (ref "K5") (pin "3") (pinfunction "3_3") (pintype "passive"))
    )
    (net (code "56") (name "Net-(JP2-Pad5)") (class "Default")
      (node (ref "JP2") (pin "5") (pinfunction "5_5") (pintype "passive"))
      (node (ref "K5") (pin "1") (pinfunction "1_1") (pintype "passive"))
    )
    (net (code "57") (name "Net-(JP2-Pad6)") (class "Default")
      (node (ref "JP2") (pin "6") (pinfunction "6_6") (pintype "passive"))
      (node (ref "K5") (pin "2") (pinfunction "2_2") (pintype "passive"))
    )
    (net (code "58") (name "Net-(JP5-Pad1)") (class "Default")
      (node (ref "JP5") (pin "1") (pinfunction "1_1") (pintype "passive"))
      (node (ref "K6") (pin "3") (pinfunction "3_3") (pintype "passive"))
    )
    (net (code "59") (name "Net-(JP5-Pad2)") (class "Default")
      (node (ref "JP5") (pin "2") (pinfunction "2_2") (pintype "passive"))
      (node (ref "K6") (pin "1") (pinfunction "1_1") (pintype "passive"))
    )
    (net (code "60") (name "Net-(JP5-Pad3)") (class "Default")
      (node (ref "JP5") (pin "3") (pinfunction "3_3") (pintype "passive"))
      (node (ref "K6") (pin "2") (pinfunction "2_2") (pintype "passive"))
    )
    (net (code "61") (name "Net-(JP5-Pad4)") (class "Default")
      (node (ref "JP5") (pin "4") (pinfunction "4_4") (pintype "passive"))
      (node (ref "K7") (pin "3") (pinfunction "3_3") (pintype "passive"))
    )
    (net (code "62") (name "Net-(JP5-Pad5)") (class "Default")
      (node (ref "JP5") (pin "5") (pinfunction "5_5") (pintype "passive"))
      (node (ref "K7") (pin "1") (pinfunction "1_1") (pintype "passive"))
    )
    (net (code "63") (name "Net-(JP5-Pad6)") (class "Default")
      (node (ref "JP5") (pin "6") (pinfunction "6_6") (pintype "passive"))
      (node (ref "K7") (pin "2") (pinfunction "2_2") (pintype "passive"))
    )
    (net (code "64") (name "Net-(Q1A-G)") (class "Default")
      (node (ref "Q1") (pin "2") (pinfunction "G_2") (pintype "passive"))
      (node (ref "R10") (pin "2") (pinfunction "2_2") (pintype "passive"))
      (node (ref "R2") (pin "2") (pinfunction "2_2") (pintype "passive"))
    )
    (net (code "65") (name "Net-(Q1B-G)") (class "Default")
      (node (ref "Q1") (pin "4") (pinfunction "G_4") (pintype "passive"))
      (node (ref "R1") (pin "2") (pinfunction "2_2") (pintype "passive"))
      (node (ref "R9") (pin "2") (pinfunction "2_2") (pintype "passive"))
    )
    (net (code "66") (name "Net-(Q3B-G)") (class "Default")
      (node (ref "Q3") (pin "4") (pinfunction "G_4") (pintype "passive"))
      (node (ref "R11") (pin "2") (pinfunction "2_2") (pintype "passive"))
      (node (ref "R3") (pin "2") (pinfunction "2_2") (pintype "passive"))
    )
    (net (code "67") (name "Net-(Q4A-G)") (class "Default")
      (node (ref "Q4") (pin "2") (pinfunction "G_2") (pintype "passive"))
      (node (ref "R13") (pin "2") (pinfunction "2_2") (pintype "passive"))
      (node (ref "R5") (pin "2") (pinfunction "2_2") (pintype "passive"))
    )
    (net (code "68") (name "Net-(Q4B-G)") (class "Default")
      (node (ref "Q4") (pin "4") (pinfunction "G_4") (pintype "passive"))
      (node (ref "R12") (pin "2") (pinfunction "2_2") (pintype "passive"))
      (node (ref "R4") (pin "2") (pinfunction "2_2") (pintype "passive"))
    )
    (net (code "69") (name "Net-(Q7A-G)") (class "Default")
      (node (ref "Q7") (pin "2") (pinfunction "G_2") (pintype "passive"))
      (node (ref "R15") (pin "2") (pinfunction "2_2") (pintype "passive"))
      (node (ref "R7") (pin "2") (pinfunction "2_2") (pintype "passive"))
    )
    (net (code "70") (name "Net-(Q7B-G)") (class "Default")
      (node (ref "Q7") (pin "4") (pinfunction "G_4") (pintype "passive"))
      (node (ref "R14") (pin "2") (pinfunction "2_2") (pintype "passive"))
      (node (ref "R6") (pin "2") (pinfunction "2_2") (pintype "passive"))
    )
    (net (code "71") (name "Net-(U3-3V3OUT)") (class "Default")
      (node (ref "C14") (pin "2") (pinfunction "2_2") (pintype "passive"))
      (node (ref "U3") (pin "17") (pinfunction "3V3OUT_17") (pintype "passive"))
      (node (ref "U3") (pin "4") (pinfunction "VCCIO_4") (pintype "passive"))
    )
    (net (code "72") (name "Net-(U3-DTR#)") (class "Default")
      (node (ref "U3") (pin "2") (pinfunction "DTR#_2") (pintype "passive"))
      (node (ref "U4") (pin "4") (pinfunction "InB_4") (pintype "passive"))
    )
    (net (code "73") (name "Net-(U3-RTS#)") (class "Default")
      (node (ref "R27") (pin "1") (pinfunction "1_1") (pintype "passive"))
      (node (ref "U3") (pin "3") (pinfunction "RTS#_3") (pintype "passive"))
    )
    (net (code "74") (name "Net-(U3-RXD)") (class "Default")
      (node (ref "U3") (pin "5") (pinfunction "RXD_5") (pintype "passive"))
      (node (ref "U4") (pin "5") (pinfunction "OutC_5") (pintype "passive"))
    )
    (net (code "75") (name "Net-(U3-TXD)") (class "Default")
      (node (ref "U3") (pin "1") (pinfunction "TXD_1") (pintype "passive"))
      (node (ref "U4") (pin "3") (pinfunction "InA_3") (pintype "passive"))
    )
    (net (code "76") (name "Net-(U3-USBDM)") (class "Default")
      (node (ref "R26") (pin "2") (pinfunction "2_2") (pintype "passive"))
      (node (ref "U3") (pin "16") (pinfunction "USBDM_16") (pintype "passive"))
    )
    (net (code "77") (name "Net-(U3-USBDP)") (class "Default")
      (node (ref "R25") (pin "2") (pinfunction "2_2") (pintype "passive"))
      (node (ref "U3") (pin "15") (pinfunction "USBDP_15") (pintype "passive"))
    )
    (net (code "78") (name "Net-(U3-VCC)") (class "Default")
      (node (ref "C12") (pin "2") (pinfunction "2_2") (pintype "passive"))
      (node (ref "R24") (pin "2") (pinfunction "2_2") (pintype "passive"))
      (node (ref "U3") (pin "20") (pinfunction "VCC_20") (pintype "passive"))
      (node (ref "U4") (pin "1") (pinfunction "Vcc1_1") (pintype "passive"))
      (node (ref "U4") (pin "7") (pinfunction "En1_7") (pintype "passive"))
      (node (ref "U5") (pin "1") (pinfunction "0_1") (pintype "passive"))
    )
    (net (code "79") (name "Net-(U5-1)") (class "Default")
      (node (ref "R27") (pin "2") (pinfunction "2_2") (pintype "passive"))
      (node (ref "U5") (pin "2") (pinfunction "1_2") (pintype "passive"))
    )
    (net (code "80") (name "Net-(U6-PV)") (class "Default")
      (node (ref "C15") (pin "2") (pinfunction "2_2") (pintype "passive"))
      (node (ref "R28") (pin "2") (pinfunction "2_2") (pintype "passive"))
      (node (ref "U6") (pin "7") (pinfunction "PV_7") (pintype "passive"))
    )
    (net (code "81") (name "Net-(U7-A)") (class "Default")
      (node (ref "JP3") (pin "3") (pinfunction "3_3") (pintype "passive"))
      (node (ref "U7") (pin "12") (pinfunction "A_12") (pintype "passive"))
    )
    (net (code "82") (name "Net-(U7-B)") (class "Default")
      (node (ref "JP3") (pin "4") (pinfunction "4_4") (pintype "passive"))
      (node (ref "U7") (pin "13") (pinfunction "B_13") (pintype "passive"))
    )
    (net (code "83") (name "Net-(U7-PV)") (class "Default")
      (node (ref "C16") (pin "2") (pinfunction "2_2") (pintype "passive"))
      (node (ref "R51") (pin "2") (pinfunction "2_2") (pintype "passive"))
      (node (ref "U7") (pin "7") (pinfunction "PV_7") (pintype "passive"))
    )
    (net (code "84") (name "Net-(U11-NC-Pad4)") (class "Default")
      (node (ref "U11") (pin "4") (pinfunction "NC_4") (pintype "passive"))
      (node (ref "U11") (pin "5") (pinfunction "NC_5") (pintype "passive"))
    )
    (net (code "85") (name "Net-(U11-OUT)") (class "Default")
      (node (ref "C44") (pin "1") (pinfunction "1_1") (pintype "passive"))
      (node (ref "U11") (pin "1") (pinfunction "OUT_1") (pintype "power_in"))
      (node (ref "U6") (pin "16") (pinfunction "Vcc2_16") (pintype "passive"))
    )
    (net (code "86") (name "Net-(U12-NC-Pad4)") (class "Default")
      (node (ref "U12") (pin "4") (pinfunction "NC_4") (pintype "passive"))
      (node (ref "U12") (pin "5") (pinfunction "NC_5") (pintype "passive"))
    )
    (net (code "87") (name "Net-(U12-OUT)") (class "Default")
      (node (ref "C46") (pin "1") (pinfunction "1_1") (pintype "passive"))
      (node (ref "U12") (pin "1") (pinfunction "OUT_1") (pintype "power_in"))
      (node (ref "U7") (pin "16") (pinfunction "Vcc2_16") (pintype "passive"))
    )
    (net (code "88") (name "unconnected-(J1-Pad4)") (class "Default")
      (node (ref "J1") (pin "4") (pinfunction "4_4") (pintype "passive"))
    )
    (net (code "89") (name "unconnected-(JP2-Pad7)") (class "Default")
      (node (ref "JP2") (pin "7") (pinfunction "7_7") (pintype "passive"))
    )
    (net (code "90") (name "unconnected-(U3-CBUS0-Pad23)") (class "Default")
      (node (ref "U3") (pin "23") (pinfunction "CBUS0_23") (pintype "passive"))
    )
    (net (code "91") (name "unconnected-(U3-CBUS1-Pad22)") (class "Default")
      (node (ref "U3") (pin "22") (pinfunction "CBUS1_22") (pintype "passive"))
    )
    (net (code "92") (name "unconnected-(U3-CBUS2-Pad13)") (class "Default")
      (node (ref "U3") (pin "13") (pinfunction "CBUS2_13") (pintype "passive"))
    )
    (net (code "93") (name "unconnected-(U3-CBUS3-Pad14)") (class "Default")
      (node (ref "U3") (pin "14") (pinfunction "CBUS3_14") (pintype "passive"))
    )
    (net (code "94") (name "unconnected-(U3-CBUS4-Pad12)") (class "Default")
      (node (ref "U3") (pin "12") (pinfunction "CBUS4_12") (pintype "passive"))
    )
    (net (code "95") (name "unconnected-(U3-CTS#-Pad11)") (class "Default")
      (node (ref "U3") (pin "11") (pinfunction "CTS#_11") (pintype "passive"))
    )
    (net (code "96") (name "unconnected-(U3-DCD#-Pad10)") (class "Default")
      (node (ref "U3") (pin "10") (pinfunction "DCD#_10") (pintype "passive"))
    )
    (net (code "97") (name "unconnected-(U3-DSR#-Pad9)") (class "Default")
      (node (ref "U3") (pin "9") (pinfunction "DSR#_9") (pintype "passive"))
    )
    (net (code "98") (name "unconnected-(U3-NC-Pad8)") (class "Default")
      (node (ref "U3") (pin "8") (pinfunction "NC_8") (pintype "passive"))
    )
    (net (code "99") (name "unconnected-(U3-NC-Pad24)") (class "Default")
      (node (ref "U3") (pin "24") (pinfunction "NC_24") (pintype "passive"))
    )
    (net (code "100") (name "unconnected-(U3-OSCI-Pad27)") (class "Default")
      (node (ref "U3") (pin "27") (pinfunction "OSCI_27") (pintype "passive"))
    )
    (net (code "101") (name "unconnected-(U3-OSCO-Pad28)") (class "Default")
      (node (ref "U3") (pin "28") (pinfunction "OSCO_28") (pintype "passive"))
    )
    (net (code "102") (name "unconnected-(U3-RESET#-Pad19)") (class "Default")
      (node (ref "U3") (pin "19") (pinfunction "RESET#_19") (pintype "passive"))
    )
    (net (code "103") (name "unconnected-(U3-RI#-Pad6)") (class "Default")
      (node (ref "U3") (pin "6") (pinfunction "RI#_6") (pintype "passive"))
    )
    (net (code "104") (name "unconnected-(U4-NC-Pad6)") (class "Default")
      (node (ref "U4") (pin "6") (pinfunction "NC_6") (pintype "passive"))
    )
    (net (code "105") (name "unconnected-(U4-NC-Pad11)") (class "Default")
      (node (ref "U4") (pin "11") (pinfunction "NC_11") (pintype "passive"))
    )
  )
)
